# base.net
KiCad netlist of a schematic drawn in EAGLE
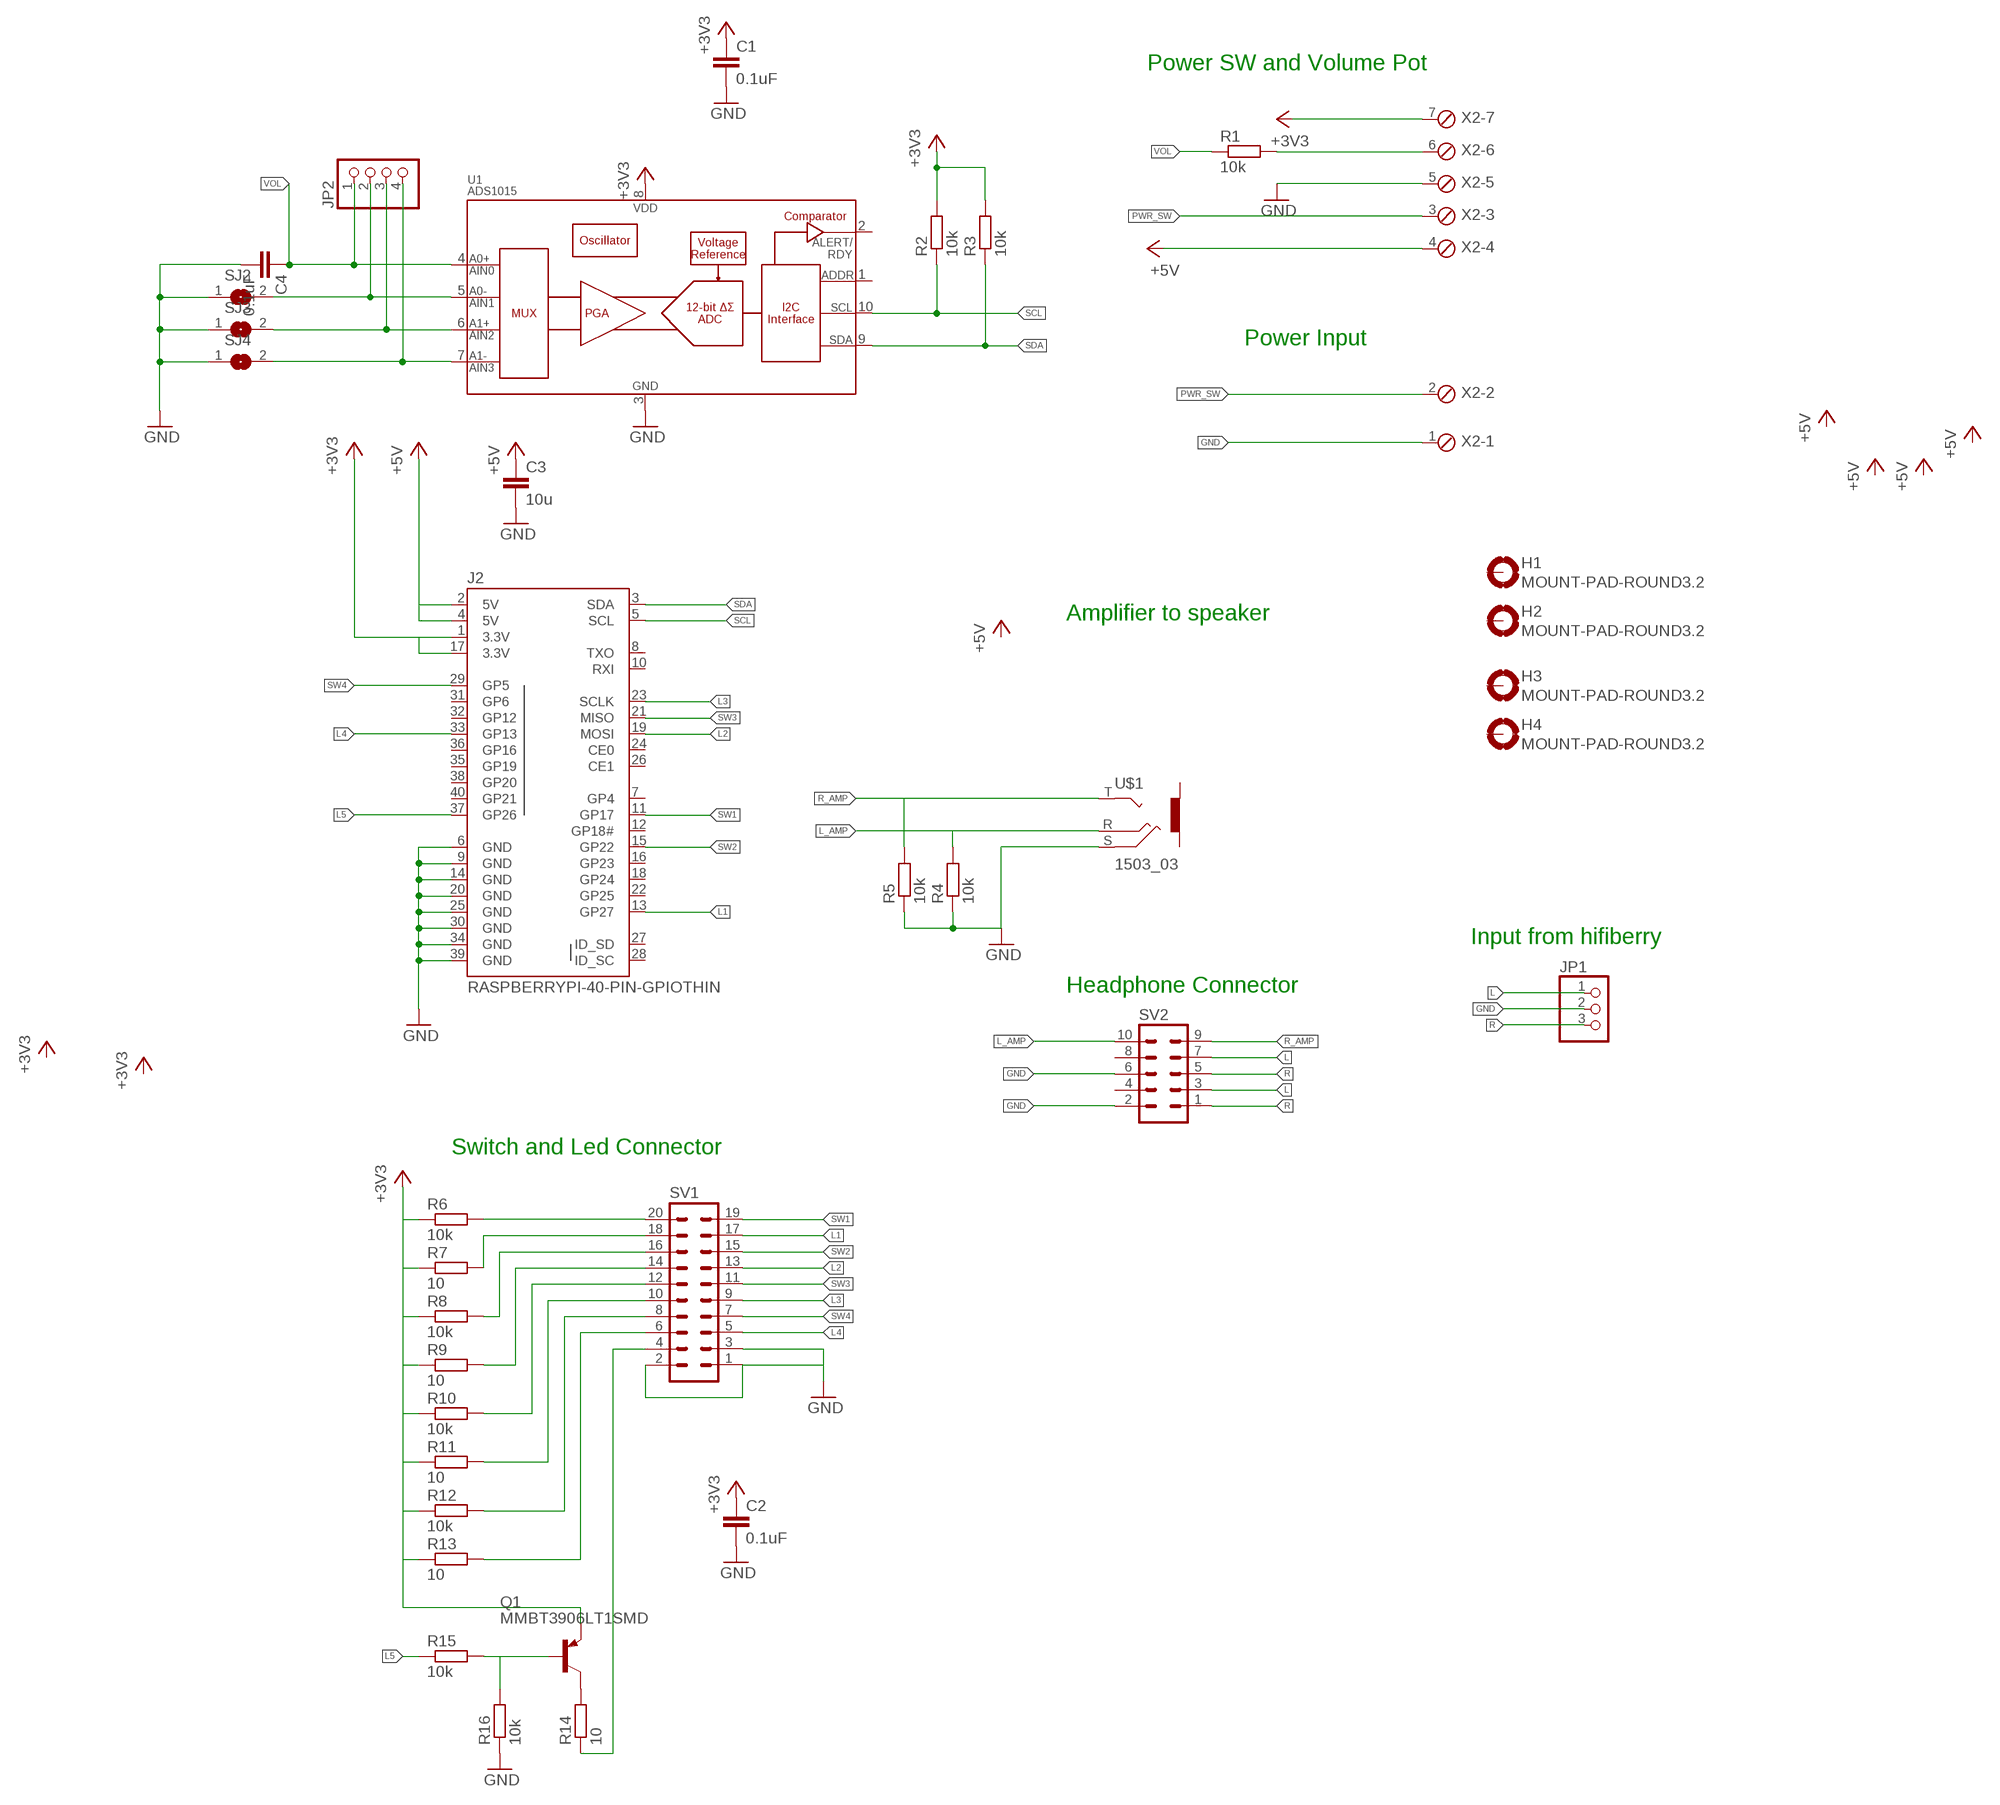
[diagram p0: schematic, sheet 1]

(export (version "E")
  (design (tool "Eeschema 10.0.6"))
  (components
    (comp (ref "C1")
      (value "0.1uF")
      (footprint "eagle-import:C0805")
      (libsource (lib "eagle-import") (part "C-EUC0805"))
    )
    (comp (ref "C2")
      (value "0.1uF")
      (footprint "eagle-import:C0805")
      (libsource (lib "eagle-import") (part "C-EUC0805"))
    )
    (comp (ref "C3")
      (value "10u")
      (footprint "eagle-import:C0805")
      (libsource (lib "eagle-import") (part "C-EUC0805"))
    )
    (comp (ref "C4")
      (value "0.1uF")
      (footprint "eagle-import:C0805")
      (libsource (lib "eagle-import") (part "C-EUC0805"))
    )
    (comp (ref "H1")
      (value "MOUNT-PAD-ROUND3.2")
      (footprint "eagle-import:3,2-PAD")
      (libsource (lib "eagle-import") (part "MOUNT-PAD-ROUND3.2"))
    )
    (comp (ref "H2")
      (value "MOUNT-PAD-ROUND3.2")
      (footprint "eagle-import:3,2-PAD")
      (libsource (lib "eagle-import") (part "MOUNT-PAD-ROUND3.2"))
    )
    (comp (ref "H3")
      (value "MOUNT-PAD-ROUND3.2")
      (footprint "eagle-import:3,2-PAD")
      (libsource (lib "eagle-import") (part "MOUNT-PAD-ROUND3.2"))
    )
    (comp (ref "H4")
      (value "MOUNT-PAD-ROUND3.2")
      (footprint "eagle-import:3,2-PAD")
      (libsource (lib "eagle-import") (part "MOUNT-PAD-ROUND3.2"))
    )
    (comp (ref "J2")
      (value "RASPBERRYPI-40-PIN-GPIOTHIN")
      (footprint "eagle-import:2X20-SHROUDED-THIN")
      (libsource (lib "eagle-import") (part "RASPBERRYPI-40-PIN-GPIOTHIN"))
    )
    (comp (ref "JP1")
      (value "PINHD-1X3")
      (footprint "eagle-import:1X03")
      (libsource (lib "eagle-import") (part "PINHD-1X3"))
    )
    (comp (ref "JP2")
      (value "PINHD-1X4")
      (footprint "eagle-import:1X04")
      (libsource (lib "eagle-import") (part "PINHD-1X4"))
    )
    (comp (ref "Q1")
      (value "MMBT3906LT1SMD")
      (footprint "eagle-import:SOT23-BEC")
      (libsource (lib "eagle-import") (part "MMBT3906SMDLT1"))
    )
    (comp (ref "R1")
      (value "10k")
      (footprint "eagle-import:R0805")
      (libsource (lib "eagle-import") (part "R-EU_R0805"))
    )
    (comp (ref "R2")
      (value "10k")
      (footprint "eagle-import:R0805")
      (libsource (lib "eagle-import") (part "R-EU_R0805"))
    )
    (comp (ref "R3")
      (value "10k")
      (footprint "eagle-import:R0805")
      (libsource (lib "eagle-import") (part "R-EU_R0805"))
    )
    (comp (ref "R4")
      (value "10k")
      (footprint "eagle-import:R0805")
      (libsource (lib "eagle-import") (part "R-EU_R0805"))
    )
    (comp (ref "R5")
      (value "10k")
      (footprint "eagle-import:R0805")
      (libsource (lib "eagle-import") (part "R-EU_R0805"))
    )
    (comp (ref "R6")
      (value "10k")
      (footprint "eagle-import:R0805")
      (libsource (lib "eagle-import") (part "R-EU_R0805"))
    )
    (comp (ref "R7")
      (value "10")
      (footprint "eagle-import:R0805")
      (libsource (lib "eagle-import") (part "R-EU_R0805"))
    )
    (comp (ref "R8")
      (value "10k")
      (footprint "eagle-import:R0805")
      (libsource (lib "eagle-import") (part "R-EU_R0805"))
    )
    (comp (ref "R9")
      (value "10")
      (footprint "eagle-import:R0805")
      (libsource (lib "eagle-import") (part "R-EU_R0805"))
    )
    (comp (ref "R10")
      (value "10k")
      (footprint "eagle-import:R0805")
      (libsource (lib "eagle-import") (part "R-EU_R0805"))
    )
    (comp (ref "R11")
      (value "10")
      (footprint "eagle-import:R0805")
      (libsource (lib "eagle-import") (part "R-EU_R0805"))
    )
    (comp (ref "R12")
      (value "10k")
      (footprint "eagle-import:R0805")
      (libsource (lib "eagle-import") (part "R-EU_R0805"))
    )
    (comp (ref "R13")
      (value "10")
      (footprint "eagle-import:R0805")
      (libsource (lib "eagle-import") (part "R-EU_R0805"))
    )
    (comp (ref "R14")
      (value "10")
      (footprint "eagle-import:R0805")
      (libsource (lib "eagle-import") (part "R-EU_R0805"))
    )
    (comp (ref "R15")
      (value "10k")
      (footprint "eagle-import:R0805")
      (libsource (lib "eagle-import") (part "R-EU_R0805"))
    )
    (comp (ref "R16")
      (value "10k")
      (footprint "eagle-import:R0805")
      (libsource (lib "eagle-import") (part "R-EU_R0805"))
    )
    (comp (ref "SJ2")
      (value "SOLDERJUMPER")
      (footprint "eagle-import:SOLDERJUMPER_ARROW_NOPASTE")
      (libsource (lib "eagle-import") (part "SOLDERJUMPER"))
    )
    (comp (ref "SJ3")
      (value "SOLDERJUMPER")
      (footprint "eagle-import:SOLDERJUMPER_ARROW_NOPASTE")
      (libsource (lib "eagle-import") (part "SOLDERJUMPER"))
    )
    (comp (ref "SJ4")
      (value "SOLDERJUMPER")
      (footprint "eagle-import:SOLDERJUMPER_ARROW_NOPASTE")
      (libsource (lib "eagle-import") (part "SOLDERJUMPER"))
    )
    (comp (ref "SV1")
      (value "ML20")
      (footprint "eagle-import:ML20")
      (libsource (lib "eagle-import") (part "ML20"))
    )
    (comp (ref "SV2")
      (value "ML10")
      (footprint "eagle-import:ML10")
      (libsource (lib "eagle-import") (part "ML10"))
    )
    (comp (ref "U$1")
      (value "1503_03")
      (footprint "eagle-import:1503_03")
      (libsource (lib "eagle-import") (part "1503_03"))
    )
    (comp (ref "U1")
      (value "ADS1015")
      (footprint "eagle-import:MSOP10")
      (libsource (lib "eagle-import") (part "ADS1015"))
    )
    (comp (ref "X2")
      (value "MPT7")
      (footprint "eagle-import:7POL254")
      (libsource (lib "eagle-import") (part "MPT7"))
    )
  )
  (nets
    (net (code "1") (name "+3V3") (class "Default")
      (node (ref "C1") (pin "1") (pinfunction "1_1") (pintype "passive"))
      (node (ref "C2") (pin "1") (pinfunction "1_1") (pintype "passive"))
      (node (ref "J2") (pin "1") (pinfunction "3.3V_1") (pintype "power_in"))
      (node (ref "J2") (pin "17") (pinfunction "3.3V_17") (pintype "power_in"))
      (node (ref "Q1") (pin "E") (pinfunction "E_E") (pintype "passive"))
      (node (ref "R10") (pin "1") (pinfunction "1_1") (pintype "passive"))
      (node (ref "R11") (pin "1") (pinfunction "1_1") (pintype "passive"))
      (node (ref "R12") (pin "1") (pinfunction "1_1") (pintype "passive"))
      (node (ref "R13") (pin "1") (pinfunction "1_1") (pintype "passive"))
      (node (ref "R2") (pin "2") (pinfunction "2_2") (pintype "passive"))
      (node (ref "R3") (pin "2") (pinfunction "2_2") (pintype "passive"))
      (node (ref "R6") (pin "1") (pinfunction "1_1") (pintype "passive"))
      (node (ref "R7") (pin "1") (pinfunction "1_1") (pintype "passive"))
      (node (ref "R8") (pin "1") (pinfunction "1_1") (pintype "passive"))
      (node (ref "R9") (pin "1") (pinfunction "1_1") (pintype "passive"))
      (node (ref "U1") (pin "8") (pinfunction "VDD_8") (pintype "bidirectional"))
      (node (ref "X2") (pin "7") (pinfunction "1_7") (pintype "passive"))
    )
    (net (code "2") (name "+5V") (class "Default")
      (node (ref "C3") (pin "1") (pinfunction "1_1") (pintype "passive"))
      (node (ref "J2") (pin "2") (pinfunction "5V_2") (pintype "power_in"))
      (node (ref "J2") (pin "4") (pinfunction "5V_4") (pintype "power_in"))
      (node (ref "X2") (pin "4") (pinfunction "1_4") (pintype "passive"))
    )
    (net (code "3") (name "GND") (class "Default")
      (node (ref "C1") (pin "2") (pinfunction "2_2") (pintype "passive"))
      (node (ref "C2") (pin "2") (pinfunction "2_2") (pintype "passive"))
      (node (ref "C3") (pin "2") (pinfunction "2_2") (pintype "passive"))
      (node (ref "C4") (pin "2") (pinfunction "2_2") (pintype "passive"))
      (node (ref "J2") (pin "14") (pinfunction "GND_14") (pintype "power_in"))
      (node (ref "J2") (pin "20") (pinfunction "GND_20") (pintype "power_in"))
      (node (ref "J2") (pin "25") (pinfunction "GND_25") (pintype "power_in"))
      (node (ref "J2") (pin "30") (pinfunction "GND_30") (pintype "power_in"))
      (node (ref "J2") (pin "34") (pinfunction "GND_34") (pintype "power_in"))
      (node (ref "J2") (pin "39") (pinfunction "GND_39") (pintype "power_in"))
      (node (ref "J2") (pin "6") (pinfunction "GND_6") (pintype "power_in"))
      (node (ref "J2") (pin "9") (pinfunction "GND_9") (pintype "power_in"))
      (node (ref "JP1") (pin "2") (pinfunction "2_2") (pintype "passive"))
      (node (ref "R16") (pin "1") (pinfunction "1_1") (pintype "passive"))
      (node (ref "R4") (pin "1") (pinfunction "1_1") (pintype "passive"))
      (node (ref "R5") (pin "1") (pinfunction "1_1") (pintype "passive"))
      (node (ref "SJ2") (pin "1") (pinfunction "1_1") (pintype "passive"))
      (node (ref "SJ3") (pin "1") (pinfunction "1_1") (pintype "passive"))
      (node (ref "SJ4") (pin "1") (pinfunction "1_1") (pintype "passive"))
      (node (ref "SV1") (pin "1") (pinfunction "1_1") (pintype "passive"))
      (node (ref "SV1") (pin "2") (pinfunction "2_2") (pintype "passive"))
      (node (ref "SV1") (pin "3") (pinfunction "3_3") (pintype "passive"))
      (node (ref "SV2") (pin "2") (pinfunction "2_2") (pintype "passive"))
      (node (ref "SV2") (pin "6") (pinfunction "6_6") (pintype "passive"))
      (node (ref "U$1") (pin "S") (pinfunction "S_S") (pintype "passive"))
      (node (ref "U1") (pin "3") (pinfunction "VSS_3") (pintype "bidirectional"))
      (node (ref "X2") (pin "1") (pinfunction "1_1") (pintype "passive"))
      (node (ref "X2") (pin "5") (pinfunction "1_5") (pintype "passive"))
    )
    (net (code "4") (name "L") (class "Default")
      (node (ref "JP1") (pin "1") (pinfunction "1_1") (pintype "passive"))
      (node (ref "SV2") (pin "3") (pinfunction "3_3") (pintype "passive"))
      (node (ref "SV2") (pin "7") (pinfunction "7_7") (pintype "passive"))
    )
    (net (code "5") (name "L1") (class "Default")
      (node (ref "J2") (pin "13") (pinfunction "GP27_13") (pintype "bidirectional"))
      (node (ref "SV1") (pin "17") (pinfunction "17_17") (pintype "passive"))
    )
    (net (code "6") (name "L2") (class "Default")
      (node (ref "J2") (pin "19") (pinfunction "MOSI_19") (pintype "output"))
      (node (ref "SV1") (pin "13") (pinfunction "13_13") (pintype "passive"))
    )
    (net (code "7") (name "L3") (class "Default")
      (node (ref "J2") (pin "23") (pinfunction "SCLK_23") (pintype "output"))
      (node (ref "SV1") (pin "9") (pinfunction "9_9") (pintype "passive"))
    )
    (net (code "8") (name "L4") (class "Default")
      (node (ref "J2") (pin "33") (pinfunction "GP13_33") (pintype "bidirectional"))
      (node (ref "SV1") (pin "5") (pinfunction "5_5") (pintype "passive"))
    )
    (net (code "9") (name "L5") (class "Default")
      (node (ref "J2") (pin "37") (pinfunction "GP26_37") (pintype "bidirectional"))
      (node (ref "R15") (pin "1") (pinfunction "1_1") (pintype "passive"))
    )
    (net (code "10") (name "L_AMP") (class "Default")
      (node (ref "R4") (pin "2") (pinfunction "2_2") (pintype "passive"))
      (node (ref "SV2") (pin "10") (pinfunction "10_10") (pintype "passive"))
      (node (ref "U$1") (pin "R") (pinfunction "R_R") (pintype "passive"))
    )
    (net (code "11") (name "Net-(Q1-PadB)") (class "Default")
      (node (ref "Q1") (pin "B") (pinfunction "B_B") (pintype "passive"))
      (node (ref "R15") (pin "2") (pinfunction "2_2") (pintype "passive"))
      (node (ref "R16") (pin "2") (pinfunction "2_2") (pintype "passive"))
    )
    (net (code "12") (name "Net-(Q1-PadC)") (class "Default")
      (node (ref "Q1") (pin "C") (pinfunction "C_C") (pintype "passive"))
      (node (ref "R14") (pin "2") (pinfunction "2_2") (pintype "passive"))
    )
    (net (code "13") (name "Net-(R6-Pad2)") (class "Default")
      (node (ref "R6") (pin "2") (pinfunction "2_2") (pintype "passive"))
      (node (ref "SV1") (pin "20") (pinfunction "20_20") (pintype "passive"))
    )
    (net (code "14") (name "Net-(R7-Pad2)") (class "Default")
      (node (ref "R7") (pin "2") (pinfunction "2_2") (pintype "passive"))
      (node (ref "SV1") (pin "18") (pinfunction "18_18") (pintype "passive"))
    )
    (net (code "15") (name "Net-(R8-Pad2)") (class "Default")
      (node (ref "R8") (pin "2") (pinfunction "2_2") (pintype "passive"))
      (node (ref "SV1") (pin "16") (pinfunction "16_16") (pintype "passive"))
    )
    (net (code "16") (name "Net-(R9-Pad2)") (class "Default")
      (node (ref "R9") (pin "2") (pinfunction "2_2") (pintype "passive"))
      (node (ref "SV1") (pin "14") (pinfunction "14_14") (pintype "passive"))
    )
    (net (code "17") (name "Net-(R10-Pad2)") (class "Default")
      (node (ref "R10") (pin "2") (pinfunction "2_2") (pintype "passive"))
      (node (ref "SV1") (pin "12") (pinfunction "12_12") (pintype "passive"))
    )
    (net (code "18") (name "Net-(R11-Pad2)") (class "Default")
      (node (ref "R11") (pin "2") (pinfunction "2_2") (pintype "passive"))
      (node (ref "SV1") (pin "10") (pinfunction "10_10") (pintype "passive"))
    )
    (net (code "19") (name "Net-(R12-Pad2)") (class "Default")
      (node (ref "R12") (pin "2") (pinfunction "2_2") (pintype "passive"))
      (node (ref "SV1") (pin "8") (pinfunction "8_8") (pintype "passive"))
    )
    (net (code "20") (name "Net-(R13-Pad2)") (class "Default")
      (node (ref "R13") (pin "2") (pinfunction "2_2") (pintype "passive"))
      (node (ref "SV1") (pin "6") (pinfunction "6_6") (pintype "passive"))
    )
    (net (code "21") (name "Net-(R14-Pad1)") (class "Default")
      (node (ref "R14") (pin "1") (pinfunction "1_1") (pintype "passive"))
      (node (ref "SV1") (pin "4") (pinfunction "4_4") (pintype "passive"))
    )
    (net (code "22") (name "Net-(U1-AIN1)") (class "Default")
      (node (ref "JP2") (pin "2") (pinfunction "2_2") (pintype "passive"))
      (node (ref "SJ2") (pin "2") (pinfunction "2_2") (pintype "passive"))
      (node (ref "U1") (pin "5") (pinfunction "AIN1_5") (pintype "bidirectional"))
    )
    (net (code "23") (name "Net-(U1-AIN2)") (class "Default")
      (node (ref "JP2") (pin "3") (pinfunction "3_3") (pintype "passive"))
      (node (ref "SJ3") (pin "2") (pinfunction "2_2") (pintype "passive"))
      (node (ref "U1") (pin "6") (pinfunction "AIN2_6") (pintype "bidirectional"))
    )
    (net (code "24") (name "Net-(U1-AIN3)") (class "Default")
      (node (ref "JP2") (pin "4") (pinfunction "4_4") (pintype "passive"))
      (node (ref "SJ4") (pin "2") (pinfunction "2_2") (pintype "passive"))
      (node (ref "U1") (pin "7") (pinfunction "AIN3_7") (pintype "bidirectional"))
    )
    (net (code "25") (name "Net-(X2F-1)") (class "Default")
      (node (ref "R1") (pin "2") (pinfunction "2_2") (pintype "passive"))
      (node (ref "X2") (pin "6") (pinfunction "1_6") (pintype "passive"))
    )
    (net (code "26") (name "PWR_SW") (class "Default")
      (node (ref "X2") (pin "2") (pinfunction "1_2") (pintype "passive"))
      (node (ref "X2") (pin "3") (pinfunction "1_3") (pintype "passive"))
    )
    (net (code "27") (name "R") (class "Default")
      (node (ref "JP1") (pin "3") (pinfunction "3_3") (pintype "passive"))
      (node (ref "SV2") (pin "1") (pinfunction "1_1") (pintype "passive"))
      (node (ref "SV2") (pin "5") (pinfunction "5_5") (pintype "passive"))
    )
    (net (code "28") (name "R_AMP") (class "Default")
      (node (ref "R5") (pin "2") (pinfunction "2_2") (pintype "passive"))
      (node (ref "SV2") (pin "9") (pinfunction "9_9") (pintype "passive"))
      (node (ref "U$1") (pin "T") (pinfunction "T_T") (pintype "passive"))
    )
    (net (code "29") (name "SCL") (class "Default")
      (node (ref "J2") (pin "5") (pinfunction "SCL_5") (pintype "bidirectional"))
      (node (ref "R2") (pin "1") (pinfunction "1_1") (pintype "passive"))
      (node (ref "U1") (pin "10") (pinfunction "SCL_10") (pintype "bidirectional"))
    )
    (net (code "30") (name "SDA") (class "Default")
      (node (ref "J2") (pin "3") (pinfunction "SDA_3") (pintype "bidirectional"))
      (node (ref "R3") (pin "1") (pinfunction "1_1") (pintype "passive"))
      (node (ref "U1") (pin "9") (pinfunction "SDA_9") (pintype "bidirectional"))
    )
    (net (code "31") (name "SW1") (class "Default")
      (node (ref "J2") (pin "11") (pinfunction "GP17_11") (pintype "bidirectional"))
      (node (ref "SV1") (pin "19") (pinfunction "19_19") (pintype "passive"))
    )
    (net (code "32") (name "SW2") (class "Default")
      (node (ref "J2") (pin "15") (pinfunction "GP22_15") (pintype "bidirectional"))
      (node (ref "SV1") (pin "15") (pinfunction "15_15") (pintype "passive"))
    )
    (net (code "33") (name "SW3") (class "Default")
      (node (ref "J2") (pin "21") (pinfunction "MISO_21") (pintype "input"))
      (node (ref "SV1") (pin "11") (pinfunction "11_11") (pintype "passive"))
    )
    (net (code "34") (name "SW4") (class "Default")
      (node (ref "J2") (pin "29") (pinfunction "GP5_29") (pintype "bidirectional"))
      (node (ref "SV1") (pin "7") (pinfunction "7_7") (pintype "passive"))
    )
    (net (code "35") (name "VOL") (class "Default")
      (node (ref "C4") (pin "1") (pinfunction "1_1") (pintype "passive"))
      (node (ref "JP2") (pin "1") (pinfunction "1_1") (pintype "passive"))
      (node (ref "R1") (pin "1") (pinfunction "1_1") (pintype "passive"))
      (node (ref "U1") (pin "4") (pinfunction "AIN0_4") (pintype "bidirectional"))
    )
    (net (code "36") (name "unconnected-(H1-MOUNT-PadB3,2)") (class "Default")
      (node (ref "H1") (pin "B3,2") (pinfunction "MOUNT_B3,2") (pintype "passive"))
    )
    (net (code "37") (name "unconnected-(H2-MOUNT-PadB3,2)") (class "Default")
      (node (ref "H2") (pin "B3,2") (pinfunction "MOUNT_B3,2") (pintype "passive"))
    )
    (net (code "38") (name "unconnected-(H3-MOUNT-PadB3,2)") (class "Default")
      (node (ref "H3") (pin "B3,2") (pinfunction "MOUNT_B3,2") (pintype "passive"))
    )
    (net (code "39") (name "unconnected-(H4-MOUNT-PadB3,2)") (class "Default")
      (node (ref "H4") (pin "B3,2") (pinfunction "MOUNT_B3,2") (pintype "passive"))
    )
    (net (code "40") (name "unconnected-(J2-CE0-Pad24)") (class "Default")
      (node (ref "J2") (pin "24") (pinfunction "CE0_24") (pintype "output"))
    )
    (net (code "41") (name "unconnected-(J2-CE1-Pad26)") (class "Default")
      (node (ref "J2") (pin "26") (pinfunction "CE1_26") (pintype "output"))
    )
    (net (code "42") (name "unconnected-(J2-GP4-Pad7)") (class "Default")
      (node (ref "J2") (pin "7") (pinfunction "GP4_7") (pintype "bidirectional"))
    )
    (net (code "43") (name "unconnected-(J2-GP6-Pad31)") (class "Default")
      (node (ref "J2") (pin "31") (pinfunction "GP6_31") (pintype "bidirectional"))
    )
    (net (code "44") (name "unconnected-(J2-GP12-Pad32)") (class "Default")
      (node (ref "J2") (pin "32") (pinfunction "GP12_32") (pintype "bidirectional"))
    )
    (net (code "45") (name "unconnected-(J2-GP16-Pad36)") (class "Default")
      (node (ref "J2") (pin "36") (pinfunction "GP16_36") (pintype "bidirectional"))
    )
    (net (code "46") (name "unconnected-(J2-GP18#-Pad12)") (class "Default")
      (node (ref "J2") (pin "12") (pinfunction "GP18#_12") (pintype "bidirectional"))
    )
    (net (code "47") (name "unconnected-(J2-GP19-Pad35)") (class "Default")
      (node (ref "J2") (pin "35") (pinfunction "GP19_35") (pintype "bidirectional"))
    )
    (net (code "48") (name "unconnected-(J2-GP20-Pad38)") (class "Default")
      (node (ref "J2") (pin "38") (pinfunction "GP20_38") (pintype "bidirectional"))
    )
    (net (code "49") (name "unconnected-(J2-GP21-Pad40)") (class "Default")
      (node (ref "J2") (pin "40") (pinfunction "GP21_40") (pintype "bidirectional"))
    )
    (net (code "50") (name "unconnected-(J2-GP23-Pad16)") (class "Default")
      (node (ref "J2") (pin "16") (pinfunction "GP23_16") (pintype "bidirectional"))
    )
    (net (code "51") (name "unconnected-(J2-GP24-Pad18)") (class "Default")
      (node (ref "J2") (pin "18") (pinfunction "GP24_18") (pintype "bidirectional"))
    )
    (net (code "52") (name "unconnected-(J2-GP25-Pad22)") (class "Default")
      (node (ref "J2") (pin "22") (pinfunction "GP25_22") (pintype "bidirectional"))
    )
    (net (code "53") (name "unconnected-(J2-ID_SC-Pad28)") (class "Default")
      (node (ref "J2") (pin "28") (pinfunction "ID_SC_28") (pintype "bidirectional"))
    )
    (net (code "54") (name "unconnected-(J2-ID_SD-Pad27)") (class "Default")
      (node (ref "J2") (pin "27") (pinfunction "ID_SD_27") (pintype "bidirectional"))
    )
    (net (code "55") (name "unconnected-(J2-RXI-Pad10)") (class "Default")
      (node (ref "J2") (pin "10") (pinfunction "RXI_10") (pintype "input"))
    )
    (net (code "56") (name "unconnected-(J2-TXO-Pad8)") (class "Default")
      (node (ref "J2") (pin "8") (pinfunction "TXO_8") (pintype "output"))
    )
    (net (code "57") (name "unconnected-(SV2-Pad4)") (class "Default")
      (node (ref "SV2") (pin "4") (pinfunction "4_4") (pintype "passive"))
    )
    (net (code "58") (name "unconnected-(SV2-Pad8)") (class "Default")
      (node (ref "SV2") (pin "8") (pinfunction "8_8") (pintype "passive"))
    )
    (net (code "59") (name "unconnected-(U$1-PadF1)") (class "Default")
      (node (ref "U$1") (pin "F1") (pinfunction "F1_F1") (pintype "passive"))
    )
    (net (code "60") (name "unconnected-(U$1-PadF2)") (class "Default")
      (node (ref "U$1") (pin "F2") (pinfunction "F2_F2") (pintype "passive"))
    )
    (net (code "61") (name "unconnected-(U1-ADDR-Pad1)") (class "Default")
      (node (ref "U1") (pin "1") (pinfunction "ADDR_1") (pintype "bidirectional"))
    )
    (net (code "62") (name "unconnected-(U1-ALERT{slash}RDY-Pad2)") (class "Default")
      (node (ref "U1") (pin "2") (pinfunction "ALERT/RDY_2") (pintype "bidirectional"))
    )
  )
)
